# 2020-05-30_00-24-191.net
KiCad netlist of a schematic drawn in Altium Designer
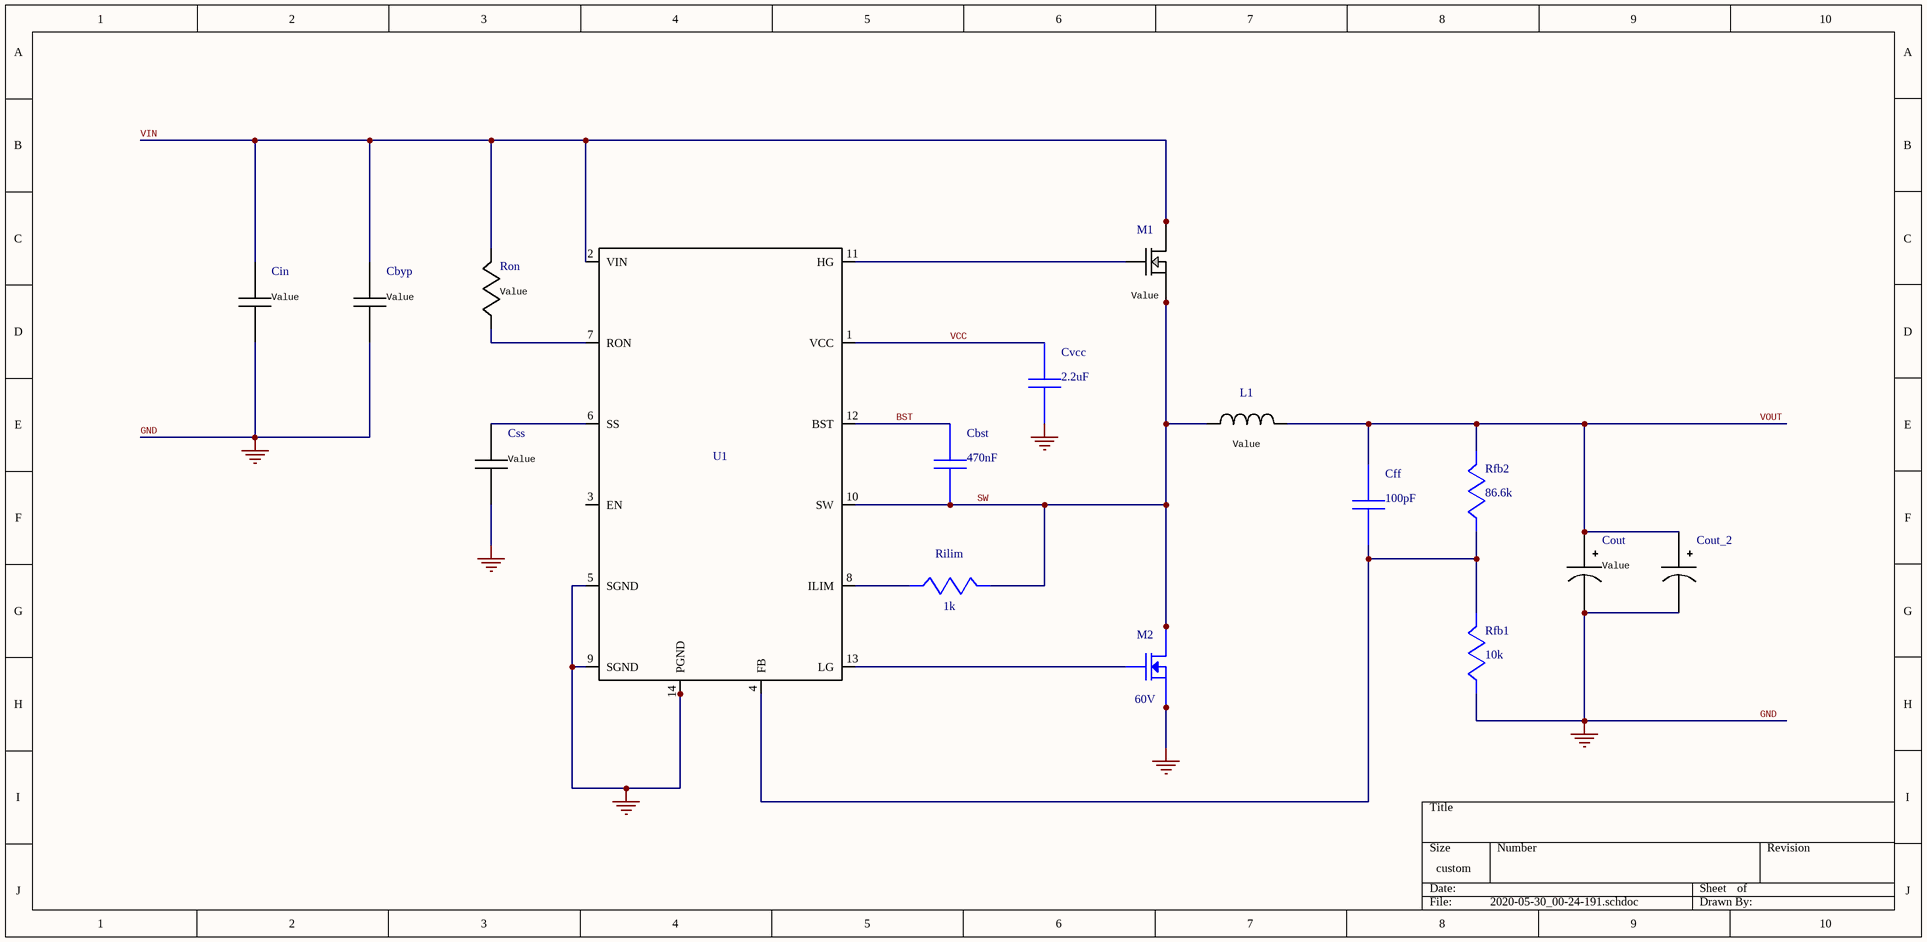
[diagram p0: 2020-05-30_00-24-191.schdoc]

(export (version "E")
  (design (tool "Eeschema 10.0.6"))
  (components
    (comp (ref "Cbst")
      (value "470nF")
      (description "ECPU1C474MA5")
      (libsource (lib "TI WEBENCH") (part "Cbst"))
    )
    (comp (ref "Cbyp")
      (value "Value")
      (footprint "0805")
      (description "Imported")
      (fields (field (name "MANUFACTURER_PART_NUMBER") "C0805C101K5GACTU"))
      (libsource (lib "2020-05-30_00-24-19") (part "C0805C101K5GACTU"))
    )
    (comp (ref "Cff")
      (value "100pF")
      (description "C0805C101K5GACTU")
      (libsource (lib "TI WEBENCH") (part "Cff"))
    )
    (comp (ref "Cin")
      (value "Value")
      (footprint "0805")
      (description "Imported")
      (fields
        (field (name "MANUFACTURER_PART_NUMBER") "C2012X5R1V106K085AC")
        (field (name "Comment") "C2012X5R1V106K08")
      )
      (libsource (lib "2020-05-30_00-24-19") (part "C2012X5R1V106K08"))
    )
    (comp (ref "Cout")
      (value "Value")
      (footprint "7343-15")
      (description "Imported")
      (fields (field (name "MANUFACTURER_PART_NUMBER") "EEFCS1A470R"))
      (libsource (lib "2020-05-30_00-24-19") (part "EEFCS1A470R"))
    )
    (comp (ref "Cout_2")
      (value "EEFCS1A470R")
      (footprint "7343-15")
      (description "Imported")
      (libsource (lib "2020-05-30_00-24-19") (part "EEFCS1A470R"))
    )
    (comp (ref "Css")
      (value "Value")
      (footprint "0805")
      (description "Imported")
      (fields
        (field (name "MANUFACTURER_PART_NUMBER") "CGA4F2C0G1H153J085AA")
        (field (name "Comment") "CGA4F2C0G1H153J0")
      )
      (libsource (lib "2020-05-30_00-24-19") (part "CGA4F2C0G1H153J0"))
    )
    (comp (ref "Cvcc")
      (value "2.2uF")
      (description "EMK212BJ225KG-T")
      (libsource (lib "TI WEBENCH") (part "Cvcc"))
    )
    (comp (ref "L1")
      (value "Value")
      (footprint "SRP1235")
      (description "Imported")
      (fields (field (name "MANUFACTURER_PART_NUMBER") "SRP1235-4R7M"))
      (libsource (lib "2020-05-30_00-24-19") (part "SRP1235-4R7M"))
    )
    (comp (ref "M1")
      (value "Value")
      (footprint "TRANS_NexFET_Q5A")
      (description "Imported")
      (fields (field (name "MANUFACTURER_PART_NUMBER") "CSD18534Q5A"))
      (libsource (lib "2020-05-30_00-24-19") (part "CSD18534Q5A"))
    )
    (comp (ref "M2") (value "60V") (description "CSD18534Q5A") (libsource (lib "TI WEBENCH") (part "M2")))
    (comp (ref "Rfb1")
      (value "10k")
      (description "CRCW080510K0FKEA")
      (libsource (lib "TI WEBENCH") (part "Rfb1"))
    )
    (comp (ref "Rfb2")
      (value "86.6k")
      (description "CRCW080586K6FKEA")
      (libsource (lib "TI WEBENCH") (part "Rfb2"))
    )
    (comp (ref "Rilim")
      (value "1k")
      (description "ERJ-6ENF1001V")
      (libsource (lib "TI WEBENCH") (part "Rilim"))
    )
    (comp (ref "Ron")
      (value "Value")
      (footprint "0805")
      (description "Imported")
      (fields (field (name "MANUFACTURER_PART_NUMBER") "CRCW080588K7FKEA"))
      (libsource (lib "2020-05-30_00-24-19") (part "CRCW080588K7FKEA"))
    )
    (comp (ref "U1")
      (value "LM3150MH/NOPB")
      (footprint "MXA14A")
      (description "Imported")
      (libsource (lib "2020-05-30_00-24-19") (part "LM3150MH/NOPB"))
    )
  )
  (nets
    (net (code "1") (name "/BST") (class "Default")
      (node (ref "Cbst") (pin "1") (pinfunction "1_1") (pintype "passive"))
      (node (ref "U1") (pin "12") (pinfunction "BST_12") (pintype "passive"))
    )
    (net (code "2") (name "/SW") (class "Default")
      (node (ref "Cbst") (pin "2") (pinfunction "2_2") (pintype "passive"))
      (node (ref "L1") (pin "1") (pinfunction "1_1") (pintype "passive"))
      (node (ref "M1") (pin "1") (pinfunction "Source_1") (pintype "passive"))
      (node (ref "M1") (pin "2") (pinfunction "Source_2") (pintype "passive"))
      (node (ref "M1") (pin "3") (pinfunction "Source_3") (pintype "passive"))
      (node (ref "M2") (pin "5") (pinfunction "Drain_5") (pintype "passive"))
      (node (ref "M2") (pin "6") (pinfunction "Drain_6") (pintype "passive"))
      (node (ref "M2") (pin "7") (pinfunction "Drain_7") (pintype "passive"))
      (node (ref "M2") (pin "8") (pinfunction "Drain_8") (pintype "passive"))
      (node (ref "M2") (pin "9") (pinfunction "Drain_9") (pintype "passive"))
      (node (ref "Rilim") (pin "1") (pinfunction "1_1") (pintype "passive"))
      (node (ref "U1") (pin "10") (pinfunction "SW_10") (pintype "passive"))
    )
    (net (code "3") (name "/VCC") (class "Default")
      (node (ref "Cvcc") (pin "1") (pinfunction "1_1") (pintype "passive"))
      (node (ref "U1") (pin "1") (pinfunction "VCC_1") (pintype "passive"))
    )
    (net (code "4") (name "/VIN") (class "Default")
      (node (ref "Cbyp") (pin "1") (pinfunction "1_1") (pintype "passive"))
      (node (ref "Cin") (pin "1") (pinfunction "1_1") (pintype "passive"))
      (node (ref "M1") (pin "5") (pinfunction "Drain_5") (pintype "passive"))
      (node (ref "M1") (pin "6") (pinfunction "Drain_6") (pintype "passive"))
      (node (ref "M1") (pin "7") (pinfunction "Drain_7") (pintype "passive"))
      (node (ref "M1") (pin "8") (pinfunction "Drain_8") (pintype "passive"))
      (node (ref "M1") (pin "9") (pinfunction "Drain_9") (pintype "passive"))
      (node (ref "Ron") (pin "1") (pinfunction "1_1") (pintype "passive"))
      (node (ref "U1") (pin "2") (pinfunction "VIN_2") (pintype "passive"))
    )
    (net (code "5") (name "/VOUT") (class "Default")
      (node (ref "Cff") (pin "1") (pinfunction "1_1") (pintype "passive"))
      (node (ref "Cout") (pin "1") (pinfunction "+_1") (pintype "passive"))
      (node (ref "Cout_2") (pin "1") (pinfunction "+_1") (pintype "passive"))
      (node (ref "L1") (pin "2") (pinfunction "2_2") (pintype "passive"))
      (node (ref "Rfb2") (pin "1") (pinfunction "1_1") (pintype "passive"))
    )
    (net (code "6") (name "0") (class "Default")
      (node (ref "Cbyp") (pin "2") (pinfunction "2_2") (pintype "passive"))
      (node (ref "Cin") (pin "2") (pinfunction "2_2") (pintype "passive"))
      (node (ref "Cout") (pin "2") (pinfunction "-_2") (pintype "passive"))
      (node (ref "Cout_2") (pin "2") (pinfunction "-_2") (pintype "passive"))
      (node (ref "Css") (pin "2") (pinfunction "2_2") (pintype "passive"))
      (node (ref "Cvcc") (pin "2") (pinfunction "2_2") (pintype "passive"))
      (node (ref "M2") (pin "1") (pinfunction "Source_1") (pintype "passive"))
      (node (ref "M2") (pin "2") (pinfunction "Source_2") (pintype "passive"))
      (node (ref "M2") (pin "3") (pinfunction "Source_3") (pintype "passive"))
      (node (ref "Rfb1") (pin "2") (pinfunction "2_2") (pintype "passive"))
      (node (ref "U1") (pin "14") (pinfunction "PGND_14") (pintype "passive"))
      (node (ref "U1") (pin "15") (pinfunction "PGND_15") (pintype "passive"))
      (node (ref "U1") (pin "5") (pinfunction "SGND_5") (pintype "passive"))
      (node (ref "U1") (pin "9") (pinfunction "SGND_9") (pintype "passive"))
    )
    (net (code "7") (name "Net-(M1-Gate)") (class "Default")
      (node (ref "M1") (pin "4") (pinfunction "Gate_4") (pintype "passive"))
      (node (ref "U1") (pin "11") (pinfunction "HG_11") (pintype "passive"))
    )
    (net (code "8") (name "Net-(M2-Gate)") (class "Default")
      (node (ref "M2") (pin "4") (pinfunction "Gate_4") (pintype "passive"))
      (node (ref "U1") (pin "13") (pinfunction "LG_13") (pintype "passive"))
    )
    (net (code "9") (name "Net-(U1-FB)") (class "Default")
      (node (ref "Cff") (pin "2") (pinfunction "2_2") (pintype "passive"))
      (node (ref "Rfb1") (pin "1") (pinfunction "1_1") (pintype "passive"))
      (node (ref "Rfb2") (pin "2") (pinfunction "2_2") (pintype "passive"))
      (node (ref "U1") (pin "4") (pinfunction "FB_4") (pintype "passive"))
    )
    (net (code "10") (name "Net-(U1-ILIM)") (class "Default")
      (node (ref "Rilim") (pin "2") (pinfunction "2_2") (pintype "passive"))
      (node (ref "U1") (pin "8") (pinfunction "ILIM_8") (pintype "passive"))
    )
    (net (code "11") (name "Net-(U1-RON)") (class "Default")
      (node (ref "Ron") (pin "2") (pinfunction "2_2") (pintype "passive"))
      (node (ref "U1") (pin "7") (pinfunction "RON_7") (pintype "passive"))
    )
    (net (code "12") (name "Net-(U1-SS)") (class "Default")
      (node (ref "Css") (pin "1") (pinfunction "1_1") (pintype "passive"))
      (node (ref "U1") (pin "6") (pinfunction "SS_6") (pintype "passive"))
    )
    (net (code "13") (name "unconnected-(U1-EN-Pad3)") (class "Default")
      (node (ref "U1") (pin "3") (pinfunction "EN_3") (pintype "passive"))
    )
  )
)
